# out8x8_2.net
KiCad netlist of a schematic drawn in EAGLE
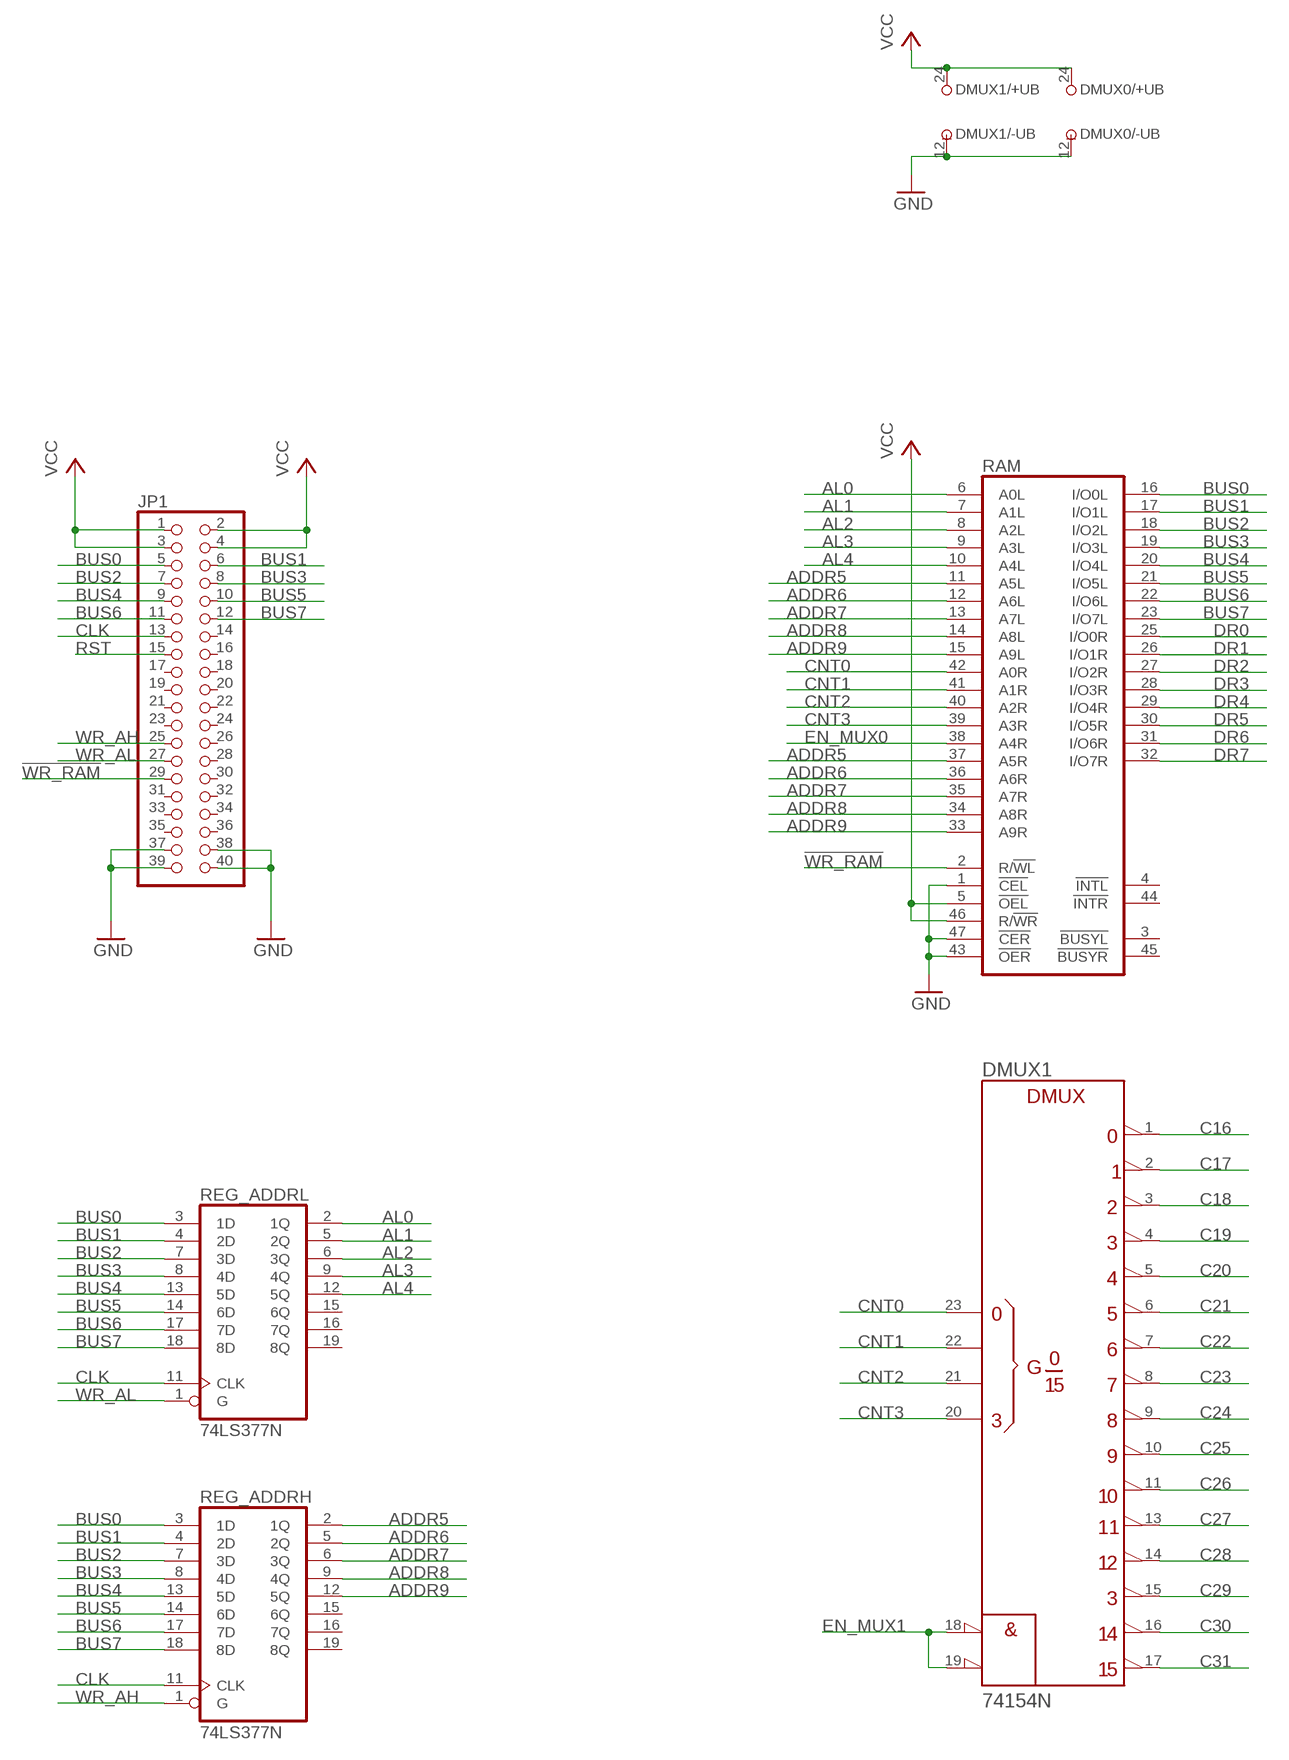
[diagram p0: schematic, sheet 1, part 1 of 2]
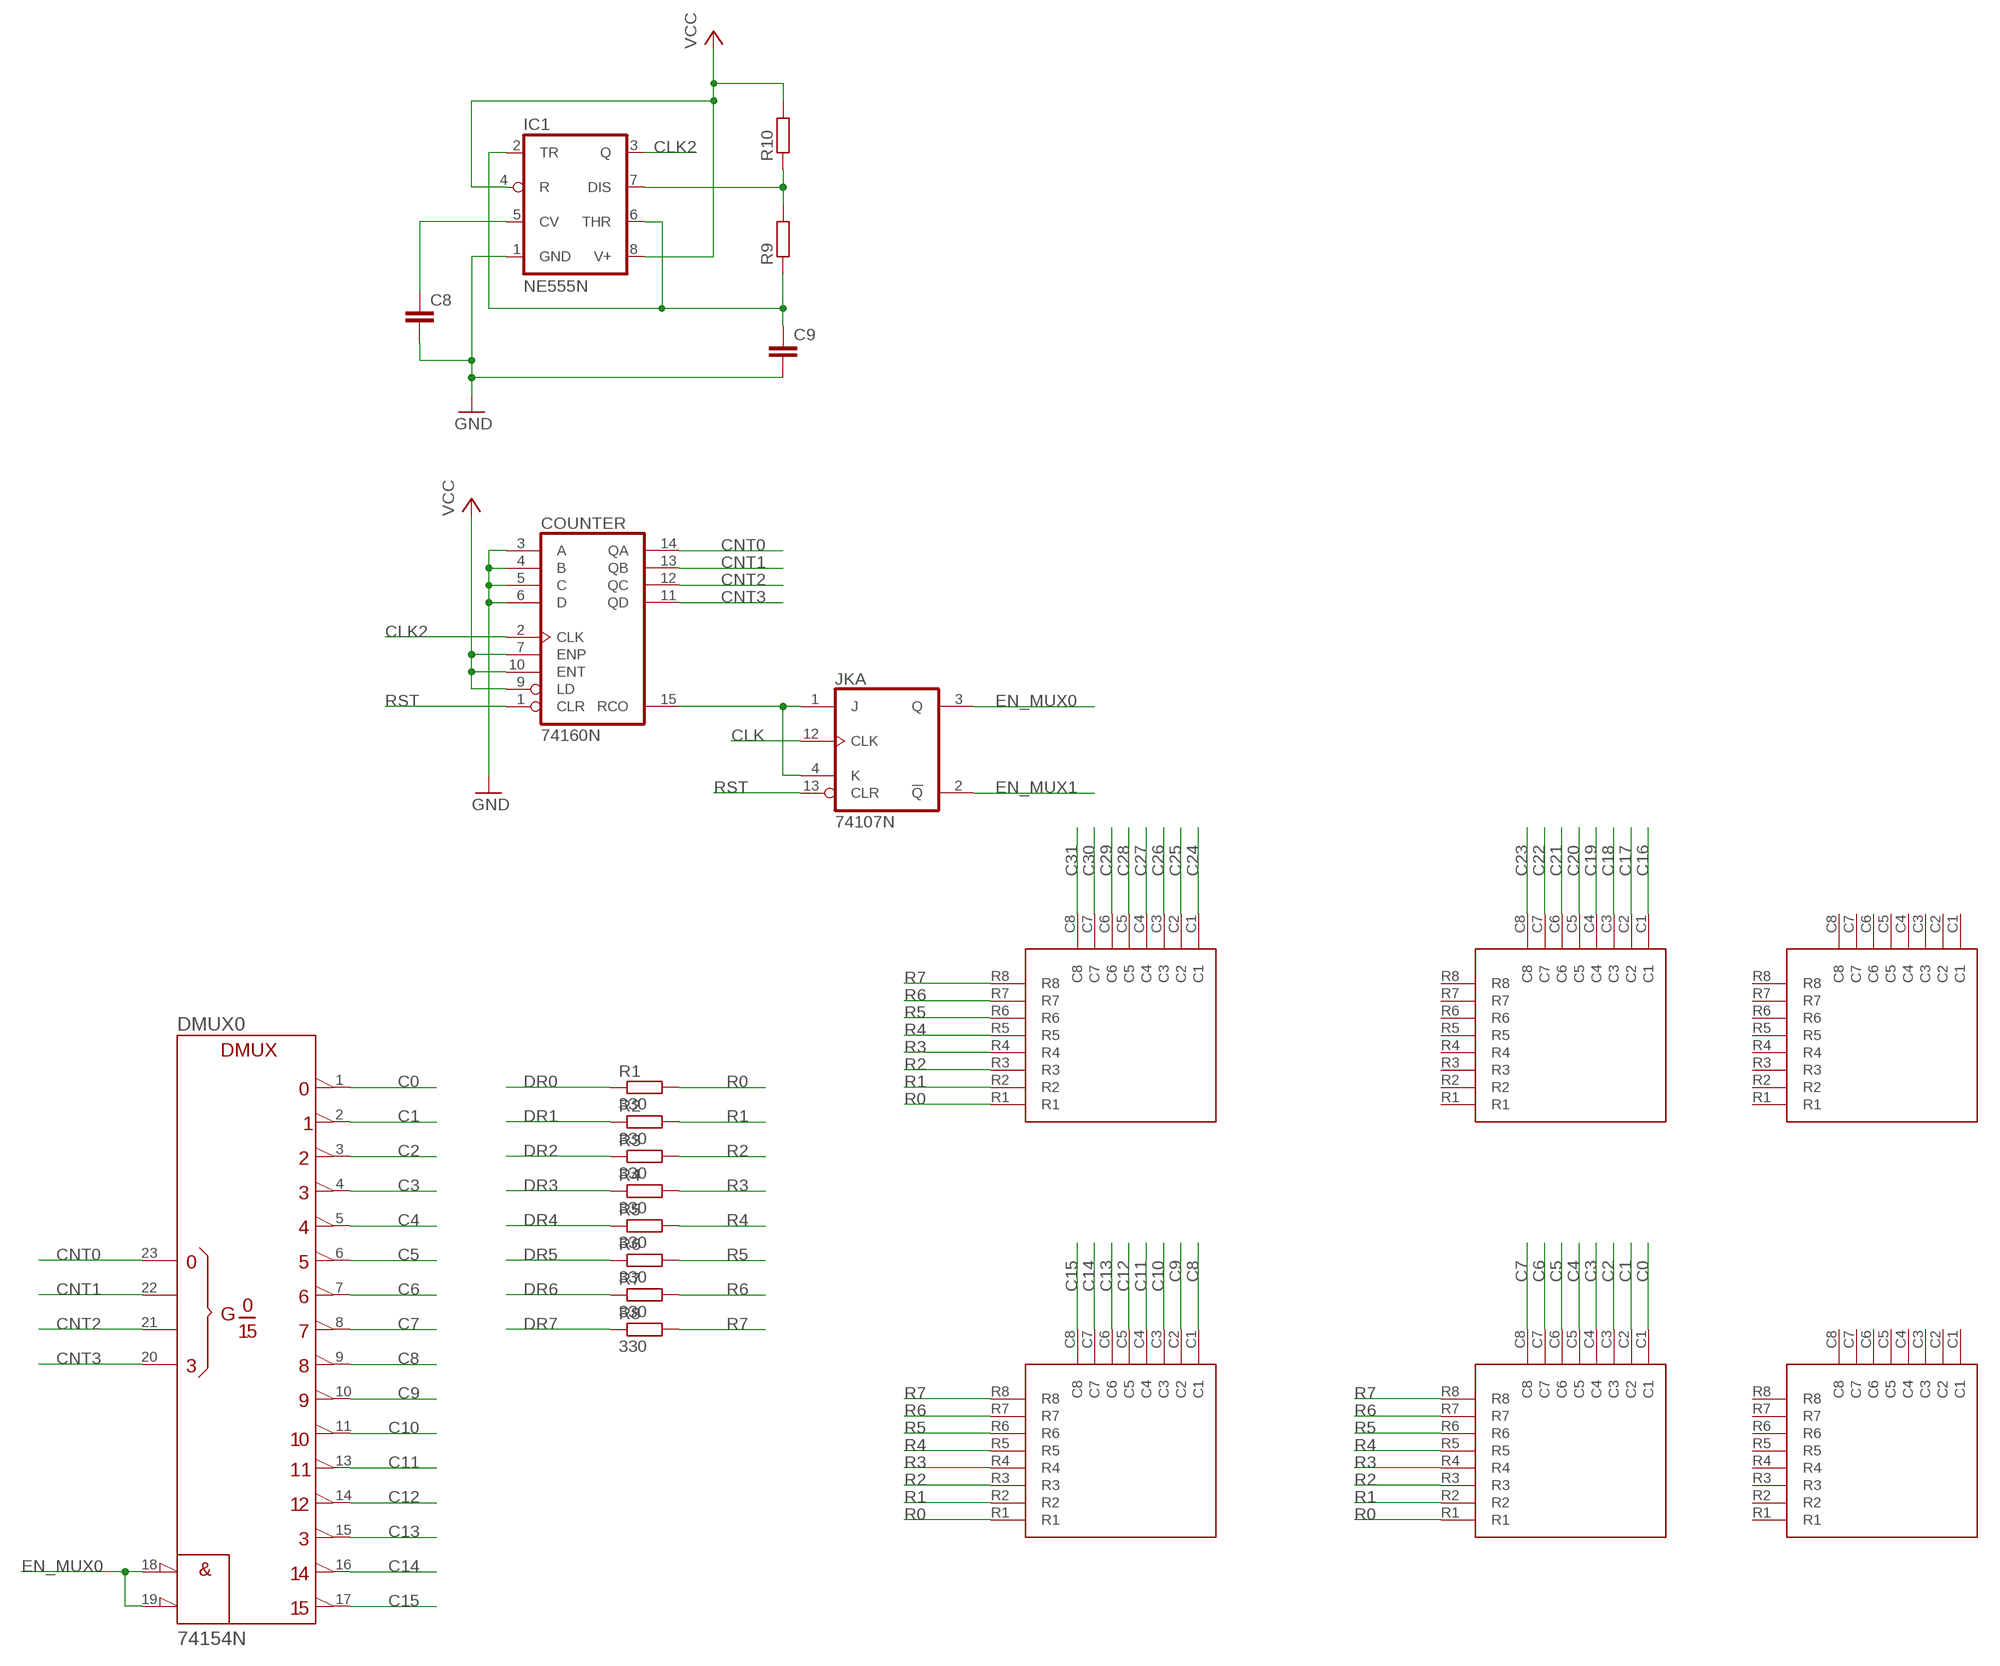
[diagram p1: schematic, sheet 1, part 2 of 2]

(export (version "E")
  (design (tool "Eeschema 10.0.6"))
  (components
    (comp (ref "C8")
      (value "C-EUC1206K")
      (footprint "eagle-import:C1206K")
      (libsource (lib "eagle-import") (part "C-EUC1206K"))
    )
    (comp (ref "C9")
      (value "C-EUC1206K")
      (footprint "eagle-import:C1206K")
      (libsource (lib "eagle-import") (part "C-EUC1206K"))
    )
    (comp (ref "COUNTER")
      (value "74160N")
      (footprint "eagle-import:DIL16")
      (libsource (lib "eagle-import") (part "74160N"))
    )
    (comp (ref "DMUX0")
      (value "74154N")
      (footprint "eagle-import:DIL24-3")
      (libsource (lib "eagle-import") (part "74154N"))
    )
    (comp (ref "DMUX1")
      (value "74154N")
      (footprint "eagle-import:DIL24-3")
      (libsource (lib "eagle-import") (part "74154N"))
    )
    (comp (ref "IC1")
      (value "NE555N")
      (footprint "eagle-import:DIL08")
      (libsource (lib "eagle-import") (part "555NNE"))
    )
    (comp (ref "JK")
      (value "74107N")
      (footprint "eagle-import:DIL14")
      (libsource (lib "eagle-import") (part "74107N"))
    )
    (comp (ref "JP1")
      (value "PINHD-2X20/90")
      (footprint "eagle-import:2X20_90")
      (libsource (lib "eagle-import") (part "PINHD-2X20/90"))
    )
    (comp (ref "R1")
      (value "330")
      (footprint "eagle-import:R0805")
      (libsource (lib "eagle-import") (part "R-EU_R0805"))
    )
    (comp (ref "R2")
      (value "330")
      (footprint "eagle-import:R0805")
      (libsource (lib "eagle-import") (part "R-EU_R0805"))
    )
    (comp (ref "R3")
      (value "330")
      (footprint "eagle-import:R0805")
      (libsource (lib "eagle-import") (part "R-EU_R0805"))
    )
    (comp (ref "R4")
      (value "330")
      (footprint "eagle-import:R0805")
      (libsource (lib "eagle-import") (part "R-EU_R0805"))
    )
    (comp (ref "R5")
      (value "330")
      (footprint "eagle-import:R0805")
      (libsource (lib "eagle-import") (part "R-EU_R0805"))
    )
    (comp (ref "R6")
      (value "330")
      (footprint "eagle-import:R0805")
      (libsource (lib "eagle-import") (part "R-EU_R0805"))
    )
    (comp (ref "R7")
      (value "330")
      (footprint "eagle-import:R0805")
      (libsource (lib "eagle-import") (part "R-EU_R0805"))
    )
    (comp (ref "R8")
      (value "330")
      (footprint "eagle-import:R0805")
      (libsource (lib "eagle-import") (part "R-EU_R0805"))
    )
    (comp (ref "R9")
      (value "R-EU_M1206")
      (footprint "eagle-import:M1206")
      (libsource (lib "eagle-import") (part "R-EU_M1206"))
    )
    (comp (ref "R10")
      (value "R-EU_M1206")
      (footprint "eagle-import:M1206")
      (libsource (lib "eagle-import") (part "R-EU_M1206"))
    )
    (comp (ref "RAM")
      (value "7130P")
      (footprint "eagle-import:DIL48")
      (libsource (lib "eagle-import") (part "7130P"))
    )
    (comp (ref "REG_ADDRH")
      (value "74LS377N")
      (footprint "eagle-import:DIL20")
      (libsource (lib "eagle-import") (part "74377NLS"))
    )
    (comp (ref "REG_ADDRL")
      (value "74LS377N")
      (footprint "eagle-import:DIL20")
      (libsource (lib "eagle-import") (part "74377NLS"))
    )
    (comp (ref "U$1")
      (value "LED8X8")
      (footprint "eagle-import:LED8X8")
      (libsource (lib "eagle-import") (part "LED8X8"))
    )
    (comp (ref "U$2")
      (value "LED8X8")
      (footprint "eagle-import:LED8X8")
      (libsource (lib "eagle-import") (part "LED8X8"))
    )
    (comp (ref "U$3")
      (value "LED8X8")
      (footprint "eagle-import:LED8X8")
      (libsource (lib "eagle-import") (part "LED8X8"))
    )
    (comp (ref "U$4")
      (value "LED8X8")
      (footprint "eagle-import:LED8X8")
      (libsource (lib "eagle-import") (part "LED8X8"))
    )
    (comp (ref "U$5")
      (value "LED8X8")
      (footprint "eagle-import:LED8X8")
      (libsource (lib "eagle-import") (part "LED8X8"))
    )
    (comp (ref "U$6")
      (value "LED8X8")
      (footprint "eagle-import:LED8X8")
      (libsource (lib "eagle-import") (part "LED8X8"))
    )
  )
  (nets
    (net (code "1") (name "/ADDR5") (class "Default")
      (node (ref "RAM") (pin "11") (pinfunction "A5L_11") (pintype "input"))
      (node (ref "RAM") (pin "37") (pinfunction "A5R_37") (pintype "input"))
      (node (ref "REG_ADDRH") (pin "2") (pinfunction "1Q_2") (pintype "output"))
    )
    (net (code "2") (name "/ADDR6") (class "Default")
      (node (ref "RAM") (pin "12") (pinfunction "A6L_12") (pintype "input"))
      (node (ref "RAM") (pin "36") (pinfunction "A6R_36") (pintype "input"))
      (node (ref "REG_ADDRH") (pin "5") (pinfunction "2Q_5") (pintype "output"))
    )
    (net (code "3") (name "/ADDR7") (class "Default")
      (node (ref "RAM") (pin "13") (pinfunction "A7L_13") (pintype "input"))
      (node (ref "RAM") (pin "35") (pinfunction "A7R_35") (pintype "input"))
      (node (ref "REG_ADDRH") (pin "6") (pinfunction "3Q_6") (pintype "output"))
    )
    (net (code "4") (name "/ADDR8") (class "Default")
      (node (ref "RAM") (pin "14") (pinfunction "A8L_14") (pintype "input"))
      (node (ref "RAM") (pin "34") (pinfunction "A8R_34") (pintype "input"))
      (node (ref "REG_ADDRH") (pin "9") (pinfunction "4Q_9") (pintype "output"))
    )
    (net (code "5") (name "/ADDR9") (class "Default")
      (node (ref "RAM") (pin "15") (pinfunction "A9L_15") (pintype "input"))
      (node (ref "RAM") (pin "33") (pinfunction "A9R_33") (pintype "input"))
      (node (ref "REG_ADDRH") (pin "12") (pinfunction "5Q_12") (pintype "output"))
    )
    (net (code "6") (name "/AL0") (class "Default")
      (node (ref "RAM") (pin "6") (pinfunction "A0L_6") (pintype "input"))
      (node (ref "REG_ADDRL") (pin "2") (pinfunction "1Q_2") (pintype "output"))
    )
    (net (code "7") (name "/AL1") (class "Default")
      (node (ref "RAM") (pin "7") (pinfunction "A1L_7") (pintype "input"))
      (node (ref "REG_ADDRL") (pin "5") (pinfunction "2Q_5") (pintype "output"))
    )
    (net (code "8") (name "/AL2") (class "Default")
      (node (ref "RAM") (pin "8") (pinfunction "A2L_8") (pintype "input"))
      (node (ref "REG_ADDRL") (pin "6") (pinfunction "3Q_6") (pintype "output"))
    )
    (net (code "9") (name "/AL3") (class "Default")
      (node (ref "RAM") (pin "9") (pinfunction "A3L_9") (pintype "input"))
      (node (ref "REG_ADDRL") (pin "9") (pinfunction "4Q_9") (pintype "output"))
    )
    (net (code "10") (name "/AL4") (class "Default")
      (node (ref "RAM") (pin "10") (pinfunction "A4L_10") (pintype "input"))
      (node (ref "REG_ADDRL") (pin "12") (pinfunction "5Q_12") (pintype "output"))
    )
    (net (code "11") (name "/BUS0") (class "Default")
      (node (ref "JP1") (pin "5") (pinfunction "5_5") (pintype "passive"))
      (node (ref "RAM") (pin "16") (pinfunction "I/O0L_16") (pintype "bidirectional"))
      (node (ref "REG_ADDRH") (pin "3") (pinfunction "1D_3") (pintype "input"))
      (node (ref "REG_ADDRL") (pin "3") (pinfunction "1D_3") (pintype "input"))
    )
    (net (code "12") (name "/BUS1") (class "Default")
      (node (ref "JP1") (pin "6") (pinfunction "6_6") (pintype "passive"))
      (node (ref "RAM") (pin "17") (pinfunction "I/O1L_17") (pintype "bidirectional"))
      (node (ref "REG_ADDRH") (pin "4") (pinfunction "2D_4") (pintype "input"))
      (node (ref "REG_ADDRL") (pin "4") (pinfunction "2D_4") (pintype "input"))
    )
    (net (code "13") (name "/BUS2") (class "Default")
      (node (ref "JP1") (pin "7") (pinfunction "7_7") (pintype "passive"))
      (node (ref "RAM") (pin "18") (pinfunction "I/O2L_18") (pintype "bidirectional"))
      (node (ref "REG_ADDRH") (pin "7") (pinfunction "3D_7") (pintype "input"))
      (node (ref "REG_ADDRL") (pin "7") (pinfunction "3D_7") (pintype "input"))
    )
    (net (code "14") (name "/BUS3") (class "Default")
      (node (ref "JP1") (pin "8") (pinfunction "8_8") (pintype "passive"))
      (node (ref "RAM") (pin "19") (pinfunction "I/O3L_19") (pintype "bidirectional"))
      (node (ref "REG_ADDRH") (pin "8") (pinfunction "4D_8") (pintype "input"))
      (node (ref "REG_ADDRL") (pin "8") (pinfunction "4D_8") (pintype "input"))
    )
    (net (code "15") (name "/BUS4") (class "Default")
      (node (ref "JP1") (pin "9") (pinfunction "9_9") (pintype "passive"))
      (node (ref "RAM") (pin "20") (pinfunction "I/O4L_20") (pintype "bidirectional"))
      (node (ref "REG_ADDRH") (pin "13") (pinfunction "5D_13") (pintype "input"))
      (node (ref "REG_ADDRL") (pin "13") (pinfunction "5D_13") (pintype "input"))
    )
    (net (code "16") (name "/BUS5") (class "Default")
      (node (ref "JP1") (pin "10") (pinfunction "10_10") (pintype "passive"))
      (node (ref "RAM") (pin "21") (pinfunction "I/O5L_21") (pintype "bidirectional"))
      (node (ref "REG_ADDRH") (pin "14") (pinfunction "6D_14") (pintype "input"))
      (node (ref "REG_ADDRL") (pin "14") (pinfunction "6D_14") (pintype "input"))
    )
    (net (code "17") (name "/BUS6") (class "Default")
      (node (ref "JP1") (pin "11") (pinfunction "11_11") (pintype "passive"))
      (node (ref "RAM") (pin "22") (pinfunction "I/O6L_22") (pintype "bidirectional"))
      (node (ref "REG_ADDRH") (pin "17") (pinfunction "7D_17") (pintype "input"))
      (node (ref "REG_ADDRL") (pin "17") (pinfunction "7D_17") (pintype "input"))
    )
    (net (code "18") (name "/BUS7") (class "Default")
      (node (ref "JP1") (pin "12") (pinfunction "12_12") (pintype "passive"))
      (node (ref "RAM") (pin "23") (pinfunction "I/O7L_23") (pintype "bidirectional"))
      (node (ref "REG_ADDRH") (pin "18") (pinfunction "8D_18") (pintype "input"))
      (node (ref "REG_ADDRL") (pin "18") (pinfunction "8D_18") (pintype "input"))
    )
    (net (code "19") (name "/C0") (class "Default")
      (node (ref "DMUX0") (pin "1") (pinfunction "0_1") (pintype "output"))
      (node (ref "U$4") (pin "C1") (pinfunction "C1_C1") (pintype "bidirectional"))
    )
    (net (code "20") (name "/C1") (class "Default")
      (node (ref "DMUX0") (pin "2") (pinfunction "1_2") (pintype "output"))
      (node (ref "U$4") (pin "C2") (pinfunction "C2_C2") (pintype "bidirectional"))
    )
    (net (code "21") (name "/C2") (class "Default")
      (node (ref "DMUX0") (pin "3") (pinfunction "2_3") (pintype "output"))
      (node (ref "U$4") (pin "C3") (pinfunction "C3_C3") (pintype "bidirectional"))
    )
    (net (code "22") (name "/C3") (class "Default")
      (node (ref "DMUX0") (pin "4") (pinfunction "3_4") (pintype "output"))
      (node (ref "U$4") (pin "C4") (pinfunction "C4_C4") (pintype "bidirectional"))
    )
    (net (code "23") (name "/C4") (class "Default")
      (node (ref "DMUX0") (pin "5") (pinfunction "4_5") (pintype "output"))
      (node (ref "U$4") (pin "C5") (pinfunction "C5_C5") (pintype "bidirectional"))
    )
    (net (code "24") (name "/C5") (class "Default")
      (node (ref "DMUX0") (pin "6") (pinfunction "5_6") (pintype "output"))
      (node (ref "U$4") (pin "C6") (pinfunction "C6_C6") (pintype "bidirectional"))
    )
    (net (code "25") (name "/C6") (class "Default")
      (node (ref "DMUX0") (pin "7") (pinfunction "6_7") (pintype "output"))
      (node (ref "U$4") (pin "C7") (pinfunction "C7_C7") (pintype "bidirectional"))
    )
    (net (code "26") (name "/C7") (class "Default")
      (node (ref "DMUX0") (pin "8") (pinfunction "7_8") (pintype "output"))
      (node (ref "U$4") (pin "C8") (pinfunction "C8_C8") (pintype "bidirectional"))
    )
    (net (code "27") (name "/C8") (class "Default")
      (node (ref "DMUX0") (pin "9") (pinfunction "8_9") (pintype "output"))
      (node (ref "U$3") (pin "C1") (pinfunction "C1_C1") (pintype "bidirectional"))
    )
    (net (code "28") (name "/C9") (class "Default")
      (node (ref "DMUX0") (pin "10") (pinfunction "9_10") (pintype "output"))
      (node (ref "U$3") (pin "C2") (pinfunction "C2_C2") (pintype "bidirectional"))
    )
    (net (code "29") (name "/C10") (class "Default")
      (node (ref "DMUX0") (pin "11") (pinfunction "10_11") (pintype "output"))
      (node (ref "U$3") (pin "C3") (pinfunction "C3_C3") (pintype "bidirectional"))
    )
    (net (code "30") (name "/C11") (class "Default")
      (node (ref "DMUX0") (pin "13") (pinfunction "11_13") (pintype "output"))
      (node (ref "U$3") (pin "C4") (pinfunction "C4_C4") (pintype "bidirectional"))
    )
    (net (code "31") (name "/C12") (class "Default")
      (node (ref "DMUX0") (pin "14") (pinfunction "12_14") (pintype "output"))
      (node (ref "U$3") (pin "C5") (pinfunction "C5_C5") (pintype "bidirectional"))
    )
    (net (code "32") (name "/C13") (class "Default")
      (node (ref "DMUX0") (pin "15") (pinfunction "13_15") (pintype "output"))
      (node (ref "U$3") (pin "C6") (pinfunction "C6_C6") (pintype "bidirectional"))
    )
    (net (code "33") (name "/C14") (class "Default")
      (node (ref "DMUX0") (pin "16") (pinfunction "14_16") (pintype "output"))
      (node (ref "U$3") (pin "C7") (pinfunction "C7_C7") (pintype "bidirectional"))
    )
    (net (code "34") (name "/C15") (class "Default")
      (node (ref "DMUX0") (pin "17") (pinfunction "15_17") (pintype "output"))
      (node (ref "U$3") (pin "C8") (pinfunction "C8_C8") (pintype "bidirectional"))
    )
    (net (code "35") (name "/C16") (class "Default")
      (node (ref "DMUX1") (pin "1") (pinfunction "0_1") (pintype "output"))
      (node (ref "U$1") (pin "C1") (pinfunction "C1_C1") (pintype "bidirectional"))
    )
    (net (code "36") (name "/C17") (class "Default")
      (node (ref "DMUX1") (pin "2") (pinfunction "1_2") (pintype "output"))
      (node (ref "U$1") (pin "C2") (pinfunction "C2_C2") (pintype "bidirectional"))
    )
    (net (code "37") (name "/C18") (class "Default")
      (node (ref "DMUX1") (pin "3") (pinfunction "2_3") (pintype "output"))
      (node (ref "U$1") (pin "C3") (pinfunction "C3_C3") (pintype "bidirectional"))
    )
    (net (code "38") (name "/C19") (class "Default")
      (node (ref "DMUX1") (pin "4") (pinfunction "3_4") (pintype "output"))
      (node (ref "U$1") (pin "C4") (pinfunction "C4_C4") (pintype "bidirectional"))
    )
    (net (code "39") (name "/C20") (class "Default")
      (node (ref "DMUX1") (pin "5") (pinfunction "4_5") (pintype "output"))
      (node (ref "U$1") (pin "C5") (pinfunction "C5_C5") (pintype "bidirectional"))
    )
    (net (code "40") (name "/C21") (class "Default")
      (node (ref "DMUX1") (pin "6") (pinfunction "5_6") (pintype "output"))
      (node (ref "U$1") (pin "C6") (pinfunction "C6_C6") (pintype "bidirectional"))
    )
    (net (code "41") (name "/C22") (class "Default")
      (node (ref "DMUX1") (pin "7") (pinfunction "6_7") (pintype "output"))
      (node (ref "U$1") (pin "C7") (pinfunction "C7_C7") (pintype "bidirectional"))
    )
    (net (code "42") (name "/C23") (class "Default")
      (node (ref "DMUX1") (pin "8") (pinfunction "7_8") (pintype "output"))
      (node (ref "U$1") (pin "C8") (pinfunction "C8_C8") (pintype "bidirectional"))
    )
    (net (code "43") (name "/C24") (class "Default")
      (node (ref "DMUX1") (pin "9") (pinfunction "8_9") (pintype "output"))
      (node (ref "U$2") (pin "C1") (pinfunction "C1_C1") (pintype "bidirectional"))
    )
    (net (code "44") (name "/C25") (class "Default")
      (node (ref "DMUX1") (pin "10") (pinfunction "9_10") (pintype "output"))
      (node (ref "U$2") (pin "C2") (pinfunction "C2_C2") (pintype "bidirectional"))
    )
    (net (code "45") (name "/C26") (class "Default")
      (node (ref "DMUX1") (pin "11") (pinfunction "10_11") (pintype "output"))
      (node (ref "U$2") (pin "C3") (pinfunction "C3_C3") (pintype "bidirectional"))
    )
    (net (code "46") (name "/C27") (class "Default")
      (node (ref "DMUX1") (pin "13") (pinfunction "11_13") (pintype "output"))
      (node (ref "U$2") (pin "C4") (pinfunction "C4_C4") (pintype "bidirectional"))
    )
    (net (code "47") (name "/C28") (class "Default")
      (node (ref "DMUX1") (pin "14") (pinfunction "12_14") (pintype "output"))
      (node (ref "U$2") (pin "C5") (pinfunction "C5_C5") (pintype "bidirectional"))
    )
    (net (code "48") (name "/C29") (class "Default")
      (node (ref "DMUX1") (pin "15") (pinfunction "13_15") (pintype "output"))
      (node (ref "U$2") (pin "C6") (pinfunction "C6_C6") (pintype "bidirectional"))
    )
    (net (code "49") (name "/C30") (class "Default")
      (node (ref "DMUX1") (pin "16") (pinfunction "14_16") (pintype "output"))
      (node (ref "U$2") (pin "C7") (pinfunction "C7_C7") (pintype "bidirectional"))
    )
    (net (code "50") (name "/C31") (class "Default")
      (node (ref "DMUX1") (pin "17") (pinfunction "15_17") (pintype "output"))
      (node (ref "U$2") (pin "C8") (pinfunction "C8_C8") (pintype "bidirectional"))
    )
    (net (code "51") (name "/CLK") (class "Default")
      (node (ref "JK") (pin "12") (pinfunction "CLK_12") (pintype "input"))
      (node (ref "JP1") (pin "13") (pinfunction "13_13") (pintype "passive"))
      (node (ref "REG_ADDRH") (pin "11") (pinfunction "CLK_11") (pintype "input"))
      (node (ref "REG_ADDRL") (pin "11") (pinfunction "CLK_11") (pintype "input"))
    )
    (net (code "52") (name "/CLK2") (class "Default")
      (node (ref "COUNTER") (pin "2") (pinfunction "CLK_2") (pintype "input"))
      (node (ref "IC1") (pin "3") (pinfunction "Q_3") (pintype "output"))
    )
    (net (code "53") (name "/CNT0") (class "Default")
      (node (ref "COUNTER") (pin "14") (pinfunction "QA_14") (pintype "output"))
      (node (ref "DMUX0") (pin "23") (pinfunction "A_23") (pintype "input"))
      (node (ref "DMUX1") (pin "23") (pinfunction "A_23") (pintype "input"))
      (node (ref "RAM") (pin "42") (pinfunction "A0R_42") (pintype "input"))
    )
    (net (code "54") (name "/CNT1") (class "Default")
      (node (ref "COUNTER") (pin "13") (pinfunction "QB_13") (pintype "output"))
      (node (ref "DMUX0") (pin "22") (pinfunction "B_22") (pintype "input"))
      (node (ref "DMUX1") (pin "22") (pinfunction "B_22") (pintype "input"))
      (node (ref "RAM") (pin "41") (pinfunction "A1R_41") (pintype "input"))
    )
    (net (code "55") (name "/CNT2") (class "Default")
      (node (ref "COUNTER") (pin "12") (pinfunction "QC_12") (pintype "output"))
      (node (ref "DMUX0") (pin "21") (pinfunction "C_21") (pintype "input"))
      (node (ref "DMUX1") (pin "21") (pinfunction "C_21") (pintype "input"))
      (node (ref "RAM") (pin "40") (pinfunction "A2R_40") (pintype "input"))
    )
    (net (code "56") (name "/CNT3") (class "Default")
      (node (ref "COUNTER") (pin "11") (pinfunction "QD_11") (pintype "output"))
      (node (ref "DMUX0") (pin "20") (pinfunction "D_20") (pintype "input"))
      (node (ref "DMUX1") (pin "20") (pinfunction "D_20") (pintype "input"))
      (node (ref "RAM") (pin "39") (pinfunction "A3R_39") (pintype "input"))
    )
    (net (code "57") (name "/DR0") (class "Default")
      (node (ref "R1") (pin "1") (pinfunction "1_1") (pintype "passive"))
      (node (ref "RAM") (pin "25") (pinfunction "I/O0R_25") (pintype "bidirectional"))
    )
    (net (code "58") (name "/DR1") (class "Default")
      (node (ref "R2") (pin "1") (pinfunction "1_1") (pintype "passive"))
      (node (ref "RAM") (pin "26") (pinfunction "I/O1R_26") (pintype "bidirectional"))
    )
    (net (code "59") (name "/DR2") (class "Default")
      (node (ref "R3") (pin "1") (pinfunction "1_1") (pintype "passive"))
      (node (ref "RAM") (pin "27") (pinfunction "I/O2R_27") (pintype "bidirectional"))
    )
    (net (code "60") (name "/DR3") (class "Default")
      (node (ref "R4") (pin "1") (pinfunction "1_1") (pintype "passive"))
      (node (ref "RAM") (pin "28") (pinfunction "I/O3R_28") (pintype "bidirectional"))
    )
    (net (code "61") (name "/DR4") (class "Default")
      (node (ref "R5") (pin "1") (pinfunction "1_1") (pintype "passive"))
      (node (ref "RAM") (pin "29") (pinfunction "I/O4R_29") (pintype "bidirectional"))
    )
    (net (code "62") (name "/DR5") (class "Default")
      (node (ref "R6") (pin "1") (pinfunction "1_1") (pintype "passive"))
      (node (ref "RAM") (pin "30") (pinfunction "I/O5R_30") (pintype "bidirectional"))
    )
    (net (code "63") (name "/DR6") (class "Default")
      (node (ref "R7") (pin "1") (pinfunction "1_1") (pintype "passive"))
      (node (ref "RAM") (pin "31") (pinfunction "I/O6R_31") (pintype "bidirectional"))
    )
    (net (code "64") (name "/DR7") (class "Default")
      (node (ref "R8") (pin "1") (pinfunction "1_1") (pintype "passive"))
      (node (ref "RAM") (pin "32") (pinfunction "I/O7R_32") (pintype "bidirectional"))
    )
    (net (code "65") (name "/EN_MUX0") (class "Default")
      (node (ref "DMUX0") (pin "18") (pinfunction "~{G1}_18") (pintype "input"))
      (node (ref "DMUX0") (pin "19") (pinfunction "~{G2}_19") (pintype "input"))
      (node (ref "JK") (pin "3") (pinfunction "Q_3") (pintype "output"))
      (node (ref "RAM") (pin "38") (pinfunction "A4R_38") (pintype "input"))
    )
    (net (code "66") (name "/EN_MUX1") (class "Default")
      (node (ref "DMUX1") (pin "18") (pinfunction "~{G1}_18") (pintype "input"))
      (node (ref "DMUX1") (pin "19") (pinfunction "~{G2}_19") (pintype "input"))
      (node (ref "JK") (pin "2") (pinfunction "~{Q}_2") (pintype "output"))
    )
    (net (code "67") (name "/R0") (class "Default")
      (node (ref "R1") (pin "2") (pinfunction "2_2") (pintype "passive"))
      (node (ref "U$2") (pin "R1") (pinfunction "R1_R1") (pintype "bidirectional"))
      (node (ref "U$3") (pin "R1") (pinfunction "R1_R1") (pintype "bidirectional"))
      (node (ref "U$4") (pin "R1") (pinfunction "R1_R1") (pintype "bidirectional"))
    )
    (net (code "68") (name "/R1") (class "Default")
      (node (ref "R2") (pin "2") (pinfunction "2_2") (pintype "passive"))
      (node (ref "U$2") (pin "R2") (pinfunction "R2_R2") (pintype "bidirectional"))
      (node (ref "U$3") (pin "R2") (pinfunction "R2_R2") (pintype "bidirectional"))
      (node (ref "U$4") (pin "R2") (pinfunction "R2_R2") (pintype "bidirectional"))
    )
    (net (code "69") (name "/R2") (class "Default")
      (node (ref "R3") (pin "2") (pinfunction "2_2") (pintype "passive"))
      (node (ref "U$2") (pin "R3") (pinfunction "R3_R3") (pintype "bidirectional"))
      (node (ref "U$3") (pin "R3") (pinfunction "R3_R3") (pintype "bidirectional"))
      (node (ref "U$4") (pin "R3") (pinfunction "R3_R3") (pintype "bidirectional"))
    )
    (net (code "70") (name "/R3") (class "Default")
      (node (ref "R4") (pin "2") (pinfunction "2_2") (pintype "passive"))
      (node (ref "U$2") (pin "R4") (pinfunction "R4_R4") (pintype "bidirectional"))
      (node (ref "U$3") (pin "R4") (pinfunction "R4_R4") (pintype "bidirectional"))
      (node (ref "U$4") (pin "R4") (pinfunction "R4_R4") (pintype "bidirectional"))
    )
    (net (code "71") (name "/R4") (class "Default")
      (node (ref "R5") (pin "2") (pinfunction "2_2") (pintype "passive"))
      (node (ref "U$2") (pin "R5") (pinfunction "R5_R5") (pintype "bidirectional"))
      (node (ref "U$3") (pin "R5") (pinfunction "R5_R5") (pintype "bidirectional"))
      (node (ref "U$4") (pin "R5") (pinfunction "R5_R5") (pintype "bidirectional"))
    )
    (net (code "72") (name "/R5") (class "Default")
      (node (ref "R6") (pin "2") (pinfunction "2_2") (pintype "passive"))
      (node (ref "U$2") (pin "R6") (pinfunction "R6_R6") (pintype "bidirectional"))
      (node (ref "U$3") (pin "R6") (pinfunction "R6_R6") (pintype "bidirectional"))
      (node (ref "U$4") (pin "R6") (pinfunction "R6_R6") (pintype "bidirectional"))
    )
    (net (code "73") (name "/R6") (class "Default")
      (node (ref "R7") (pin "2") (pinfunction "2_2") (pintype "passive"))
      (node (ref "U$2") (pin "R7") (pinfunction "R7_R7") (pintype "bidirectional"))
      (node (ref "U$3") (pin "R7") (pinfunction "R7_R7") (pintype "bidirectional"))
      (node (ref "U$4") (pin "R7") (pinfunction "R7_R7") (pintype "bidirectional"))
    )
    (net (code "74") (name "/R7") (class "Default")
      (node (ref "R8") (pin "2") (pinfunction "2_2") (pintype "passive"))
      (node (ref "U$2") (pin "R8") (pinfunction "R8_R8") (pintype "bidirectional"))
      (node (ref "U$3") (pin "R8") (pinfunction "R8_R8") (pintype "bidirectional"))
      (node (ref "U$4") (pin "R8") (pinfunction "R8_R8") (pintype "bidirectional"))
    )
    (net (code "75") (name "/RST") (class "Default")
      (node (ref "COUNTER") (pin "1") (pinfunction "CLR_1") (pintype "input"))
      (node (ref "JK") (pin "13") (pinfunction "CLR_13") (pintype "input"))
      (node (ref "JP1") (pin "15") (pinfunction "15_15") (pintype "passive"))
    )
    (net (code "76") (name "/WR_AH") (class "Default")
      (node (ref "JP1") (pin "25") (pinfunction "25_25") (pintype "passive"))
      (node (ref "REG_ADDRH") (pin "1") (pinfunction "G_1") (pintype "input"))
    )
    (net (code "77") (name "/WR_AL") (class "Default")
      (node (ref "JP1") (pin "27") (pinfunction "27_27") (pintype "passive"))
      (node (ref "REG_ADDRL") (pin "1") (pinfunction "G_1") (pintype "input"))
    )
    (net (code "78") (name "/~{WR_RAM}") (class "Default")
      (node (ref "JP1") (pin "29") (pinfunction "29_29") (pintype "passive"))
      (node (ref "RAM") (pin "2") (pinfunction "R/~{WL}_2") (pintype "input"))
    )
    (net (code "79") (name "GND") (class "Default")
      (node (ref "C8") (pin "2") (pinfunction "2_2") (pintype "passive"))
      (node (ref "C9") (pin "2") (pinfunction "2_2") (pintype "passive"))
      (node (ref "COUNTER") (pin "3") (pinfunction "A_3") (pintype "input"))
      (node (ref "COUNTER") (pin "4") (pinfunction "B_4") (pintype "input"))
      (node (ref "COUNTER") (pin "5") (pinfunction "C_5") (pintype "input"))
      (node (ref "COUNTER") (pin "6") (pinfunction "D_6") (pintype "input"))
      (node (ref "DMUX0") (pin "12") (pinfunction "-UB_12") (pintype "power_in"))
      (node (ref "DMUX1") (pin "12") (pinfunction "-UB_12") (pintype "power_in"))
      (node (ref "IC1") (pin "1") (pinfunction "GND_1") (pintype "power_in"))
      (node (ref "JP1") (pin "37") (pinfunction "37_37") (pintype "passive"))
      (node (ref "JP1") (pin "38") (pinfunction "38_38") (pintype "passive"))
      (node (ref "JP1") (pin "39") (pinfunction "39_39") (pintype "passive"))
      (node (ref "JP1") (pin "40") (pinfunction "40_40") (pintype "passive"))
      (node (ref "RAM") (pin "1") (pinfunction "~{CEL}_1") (pintype "input"))
      (node (ref "RAM") (pin "43") (pinfunction "~{OER}_43") (pintype "input"))
      (node (ref "RAM") (pin "47") (pinfunction "~{CER}_47") (pintype "input"))
    )
    (net (code "80") (name "Net-(COUNTERA-RCO)") (class "Default")
      (node (ref "COUNTER") (pin "15") (pinfunction "RCO_15") (pintype "output"))
      (node (ref "JK") (pin "1") (pinfunction "J_1") (pintype "input"))
      (node (ref "JK") (pin "4") (pinfunction "K_4") (pintype "input"))
    )
    (net (code "81") (name "Net-(IC1-CV)") (class "Default")
      (node (ref "C8") (pin "1") (pinfunction "1_1") (pintype "passive"))
      (node (ref "IC1") (pin "5") (pinfunction "CV_5") (pintype "input"))
    )
    (net (code "82") (name "Net-(IC1-DIS)") (class "Default")
      (node (ref "IC1") (pin "7") (pinfunction "DIS_7") (pintype "input"))
      (node (ref "R10") (pin "1") (pinfunction "1_1") (pintype "passive"))
      (node (ref "R9") (pin "2") (pinfunction "2_2") (pintype "passive"))
    )
    (net (code "83") (name "Net-(IC1-THR)") (class "Default")
      (node (ref "C9") (pin "1") (pinfunction "1_1") (pintype "passive"))
      (node (ref "IC1") (pin "2") (pinfunction "TR_2") (pintype "input"))
      (node (ref "IC1") (pin "6") (pinfunction "THR_6") (pintype "input"))
      (node (ref "R9") (pin "1") (pinfunction "1_1") (pintype "passive"))
    )
    (net (code "84") (name "VCC") (class "Default")
      (node (ref "COUNTER") (pin "10") (pinfunction "ENT_10") (pintype "input"))
      (node (ref "COUNTER") (pin "7") (pinfunction "ENP_7") (pintype "input"))
      (node (ref "COUNTER") (pin "9") (pinfunction "LD_9") (pintype "input"))
      (node (ref "DMUX0") (pin "24") (pinfunction "+UB_24") (pintype "power_in"))
      (node (ref "DMUX1") (pin "24") (pinfunction "+UB_24") (pintype "power_in"))
      (node (ref "IC1") (pin "4") (pinfunction "R_4") (pintype "input"))
      (node (ref "IC1") (pin "8") (pinfunction "V+_8") (pintype "power_in"))
      (node (ref "JP1") (pin "1") (pinfunction "1_1") (pintype "passive"))
      (node (ref "JP1") (pin "2") (pinfunction "2_2") (pintype "passive"))
      (node (ref "JP1") (pin "3") (pinfunction "3_3") (pintype "passive"))
      (node (ref "JP1") (pin "4") (pinfunction "4_4") (pintype "passive"))
      (node (ref "R10") (pin "2") (pinfunction "2_2") (pintype "passive"))
      (node (ref "RAM") (pin "46") (pinfunction "R/~{WR}_46") (pintype "input"))
      (node (ref "RAM") (pin "5") (pinfunction "~{OEL}_5") (pintype "input"))
    )
    (net (code "85") (name "unconnected-(JP1-Pad14)") (class "Default")
      (node (ref "JP1") (pin "14") (pinfunction "14_14") (pintype "passive"))
    )
    (net (code "86") (name "unconnected-(JP1-Pad16)") (class "Default")
      (node (ref "JP1") (pin "16") (pinfunction "16_16") (pintype "passive"))
    )
    (net (code "87") (name "unconnected-(JP1-Pad17)") (class "Default")
      (node (ref "JP1") (pin "17") (pinfunction "17_17") (pintype "passive"))
    )
    (net (code "88") (name "unconnected-(JP1-Pad18)") (class "Default")
      (node (ref "JP1") (pin "18") (pinfunction "18_18") (pintype "passive"))
    )
    (net (code "89") (name "unconnected-(JP1-Pad19)") (class "Default")
      (node (ref "JP1") (pin "19") (pinfunction "19_19") (pintype "passive"))
    )
    (net (code "90") (name "unconnected-(JP1-Pad20)") (class "Default")
      (node (ref "JP1") (pin "20") (pinfunction "20_20") (pintype "passive"))
    )
    (net (code "91") (name "unconnected-(JP1-Pad21)") (class "Default")
      (node (ref "JP1") (pin "21") (pinfunction "21_21") (pintype "passive"))
    )
    (net (code "92") (name "unconnected-(JP1-Pad22)") (class "Default")
      (node (ref "JP1") (pin "22") (pinfunction "22_22") (pintype "passive"))
    )
    (net (code "93") (name "unconnected-(JP1-Pad23)") (class "Default")
      (node (ref "JP1") (pin "23") (pinfunction "23_23") (pintype "passive"))
    )
    (net (code "94") (name "unconnected-(JP1-Pad24)") (class "Default")
      (node (ref "JP1") (pin "24") (pinfunction "24_24") (pintype "passive"))
    )
    (net (code "95") (name "unconnected-(JP1-Pad26)") (class "Default")
      (node (ref "JP1") (pin "26") (pinfunction "26_26") (pintype "passive"))
    )
    (net (code "96") (name "unconnected-(JP1-Pad28)") (class "Default")
      (node (ref "JP1") (pin "28") (pinfunction "28_28") (pintype "passive"))
    )
    (net (code "97") (name "unconnected-(JP1-Pad30)") (class "Default")
      (node (ref "JP1") (pin "30") (pinfunction "30_30") (pintype "passive"))
    )
    (net (code "98") (name "unconnected-(JP1-Pad31)") (class "Default")
      (node (ref "JP1") (pin "31") (pinfunction "31_31") (pintype "passive"))
    )
    (net (code "99") (name "unconnected-(JP1-Pad32)") (class "Default")
      (node (ref "JP1") (pin "32") (pinfunction "32_32") (pintype "passive"))
    )
    (net (code "100") (name "unconnected-(JP1-Pad33)") (class "Default")
      (node (ref "JP1") (pin "33") (pinfunction "33_33") (pintype "passive"))
    )
    (net (code "101") (name "unconnected-(JP1-Pad34)") (class "Default")
      (node (ref "JP1") (pin "34") (pinfunction "34_34") (pintype "passive"))
    )
    (net (code "102") (name "unconnected-(JP1-Pad35)") (class "Default")
      (node (ref "JP1") (pin "35") (pinfunction "35_35") (pintype "passive"))
    )
    (net (code "103") (name "unconnected-(JP1-Pad36)") (class "Default")
      (node (ref "JP1") (pin "36") (pinfunction "36_36") (pintype "passive"))
    )
    (net (code "104") (name "unconnected-(RAMA-~{BUSYL}-Pad3)") (class "Default")
      (node (ref "RAM") (pin "3") (pinfunction "~{BUSYL}_3") (pintype "bidirectional"))
    )
    (net (code "105") (name "unconnected-(RAMA-~{BUSYR}-Pad45)") (class "Default")
      (node (ref "RAM") (pin "45") (pinfunction "~{BUSYR}_45") (pintype "bidirectional"))
    )
    (net (code "106") (name "unconnected-(RAMA-~{INTL}-Pad4)") (class "Default")
      (node (ref "RAM") (pin "4") (pinfunction "~{INTL}_4") (pintype "output"))
    )
    (net (code "107") (name "unconnected-(RAMA-~{INTR}-Pad44)") (class "Default")
      (node (ref "RAM") (pin "44") (pinfunction "~{INTR}_44") (pintype "output"))
    )
    (net (code "108") (name "unconnected-(REG_ADDRHA-6Q-Pad15)") (class "Default")
      (node (ref "REG_ADDRH") (pin "15") (pinfunction "6Q_15") (pintype "output"))
    )
    (net (code "109") (name "unconnected-(REG_ADDRHA-7Q-Pad16)") (class "Default")
      (node (ref "REG_ADDRH") (pin "16") (pinfunction "7Q_16") (pintype "output"))
    )
    (net (code "110") (name "unconnected-(REG_ADDRHA-8Q-Pad19)") (class "Default")
      (node (ref "REG_ADDRH") (pin "19") (pinfunction "8Q_19") (pintype "output"))
    )
    (net (code "111") (name "unconnected-(REG_ADDRLA-6Q-Pad15)") (class "Default")
      (node (ref "REG_ADDRL") (pin "15") (pinfunction "6Q_15") (pintype "output"))
    )
    (net (code "112") (name "unconnected-(REG_ADDRLA-7Q-Pad16)") (class "Default")
      (node (ref "REG_ADDRL") (pin "16") (pinfunction "7Q_16") (pintype "output"))
    )
    (net (code "113") (name "unconnected-(REG_ADDRLA-8Q-Pad19)") (class "Default")
      (node (ref "REG_ADDRL") (pin "19") (pinfunction "8Q_19") (pintype "output"))
    )
    (net (code "114") (name "unconnected-(U$1-PadR1)") (class "Default")
      (node (ref "U$1") (pin "R1") (pinfunction "R1_R1") (pintype "bidirectional"))
    )
    (net (code "115") (name "unconnected-(U$1-PadR2)") (class "Default")
      (node (ref "U$1") (pin "R2") (pinfunction "R2_R2") (pintype "bidirectional"))
    )
    (net (code "116") (name "unconnected-(U$1-PadR3)") (class "Default")
      (node (ref "U$1") (pin "R3") (pinfunction "R3_R3") (pintype "bidirectional"))
    )
    (net (code "117") (name "unconnected-(U$1-PadR4)") (class "Default")
      (node (ref "U$1") (pin "R4") (pinfunction "R4_R4") (pintype "bidirectional"))
    )
    (net (code "118") (name "unconnected-(U$1-PadR5)") (class "Default")
      (node (ref "U$1") (pin "R5") (pinfunction "R5_R5") (pintype "bidirectional"))
    )
    (net (code "119") (name "unconnected-(U$1-PadR6)") (class "Default")
      (node (ref "U$1") (pin "R6") (pinfunction "R6_R6") (pintype "bidirectional"))
    )
    (net (code "120") (name "unconnected-(U$1-PadR7)") (class "Default")
      (node (ref "U$1") (pin "R7") (pinfunction "R7_R7") (pintype "bidirectional"))
    )
    (net (code "121") (name "unconnected-(U$1-PadR8)") (class "Default")
      (node (ref "U$1") (pin "R8") (pinfunction "R8_R8") (pintype "bidirectional"))
    )
    (net (code "122") (name "unconnected-(U$5-PadC1)") (class "Default")
      (node (ref "U$5") (pin "C1") (pinfunction "C1_C1") (pintype "bidirectional"))
    )
    (net (code "123") (name "unconnected-(U$5-PadC2)") (class "Default")
      (node (ref "U$5") (pin "C2") (pinfunction "C2_C2") (pintype "bidirectional"))
    )
    (net (code "124") (name "unconnected-(U$5-PadC3)") (class "Default")
      (node (ref "U$5") (pin "C3") (pinfunction "C3_C3") (pintype "bidirectional"))
    )
    (net (code "125") (name "unconnected-(U$5-PadC4)") (class "Default")
      (node (ref "U$5") (pin "C4") (pinfunction "C4_C4") (pintype "bidirectional"))
    )
    (net (code "126") (name "unconnected-(U$5-PadC5)") (class "Default")
      (node (ref "U$5") (pin "C5") (pinfunction "C5_C5") (pintype "bidirectional"))
    )
    (net (code "127") (name "unconnected-(U$5-PadC6)") (class "Default")
      (node (ref "U$5") (pin "C6") (pinfunction "C6_C6") (pintype "bidirectional"))
    )
    (net (code "128") (name "unconnected-(U$5-PadC7)") (class "Default")
      (node (ref "U$5") (pin "C7") (pinfunction "C7_C7") (pintype "bidirectional"))
    )
    (net (code "129") (name "unconnected-(U$5-PadC8)") (class "Default")
      (node (ref "U$5") (pin "C8") (pinfunction "C8_C8") (pintype "bidirectional"))
    )
    (net (code "130") (name "unconnected-(U$5-PadR1)") (class "Default")
      (node (ref "U$5") (pin "R1") (pinfunction "R1_R1") (pintype "bidirectional"))
    )
    (net (code "131") (name "unconnected-(U$5-PadR2)") (class "Default")
      (node (ref "U$5") (pin "R2") (pinfunction "R2_R2") (pintype "bidirectional"))
    )
    (net (code "132") (name "unconnected-(U$5-PadR3)") (class "Default")
      (node (ref "U$5") (pin "R3") (pinfunction "R3_R3") (pintype "bidirectional"))
    )
    (net (code "133") (name "unconnected-(U$5-PadR4)") (class "Default")
      (node (ref "U$5") (pin "R4") (pinfunction "R4_R4") (pintype "bidirectional"))
    )
    (net (code "134") (name "unconnected-(U$5-PadR5)") (class "Default")
      (node (ref "U$5") (pin "R5") (pinfunction "R5_R5") (pintype "bidirectional"))
    )
    (net (code "135") (name "unconnected-(U$5-PadR6)") (class "Default")
      (node (ref "U$5") (pin "R6") (pinfunction "R6_R6") (pintype "bidirectional"))
    )
    (net (code "136") (name "unconnected-(U$5-PadR7)") (class "Default")
      (node (ref "U$5") (pin "R7") (pinfunction "R7_R7") (pintype "bidirectional"))
    )
    (net (code "137") (name "unconnected-(U$5-PadR8)") (class "Default")
      (node (ref "U$5") (pin "R8") (pinfunction "R8_R8") (pintype "bidirectional"))
    )
    (net (code "138") (name "unconnected-(U$6-PadC1)") (class "Default")
      (node (ref "U$6") (pin "C1") (pinfunction "C1_C1") (pintype "bidirectional"))
    )
    (net (code "139") (name "unconnected-(U$6-PadC2)") (class "Default")
      (node (ref "U$6") (pin "C2") (pinfunction "C2_C2") (pintype "bidirectional"))
    )
    (net (code "140") (name "unconnected-(U$6-PadC3)") (class "Default")
      (node (ref "U$6") (pin "C3") (pinfunction "C3_C3") (pintype "bidirectional"))
    )
    (net (code "141") (name "unconnected-(U$6-PadC4)") (class "Default")
      (node (ref "U$6") (pin "C4") (pinfunction "C4_C4") (pintype "bidirectional"))
    )
    (net (code "142") (name "unconnected-(U$6-PadC5)") (class "Default")
      (node (ref "U$6") (pin "C5") (pinfunction "C5_C5") (pintype "bidirectional"))
    )
    (net (code "143") (name "unconnected-(U$6-PadC6)") (class "Default")
      (node (ref "U$6") (pin "C6") (pinfunction "C6_C6") (pintype "bidirectional"))
    )
    (net (code "144") (name "unconnected-(U$6-PadC7)") (class "Default")
      (node (ref "U$6") (pin "C7") (pinfunction "C7_C7") (pintype "bidirectional"))
    )
    (net (code "145") (name "unconnected-(U$6-PadC8)") (class "Default")
      (node (ref "U$6") (pin "C8") (pinfunction "C8_C8") (pintype "bidirectional"))
    )
    (net (code "146") (name "unconnected-(U$6-PadR1)") (class "Default")
      (node (ref "U$6") (pin "R1") (pinfunction "R1_R1") (pintype "bidirectional"))
    )
    (net (code "147") (name "unconnected-(U$6-PadR2)") (class "Default")
      (node (ref "U$6") (pin "R2") (pinfunction "R2_R2") (pintype "bidirectional"))
    )
    (net (code "148") (name "unconnected-(U$6-PadR3)") (class "Default")
      (node (ref "U$6") (pin "R3") (pinfunction "R3_R3") (pintype "bidirectional"))
    )
    (net (code "149") (name "unconnected-(U$6-PadR4)") (class "Default")
      (node (ref "U$6") (pin "R4") (pinfunction "R4_R4") (pintype "bidirectional"))
    )
    (net (code "150") (name "unconnected-(U$6-PadR5)") (class "Default")
      (node (ref "U$6") (pin "R5") (pinfunction "R5_R5") (pintype "bidirectional"))
    )
    (net (code "151") (name "unconnected-(U$6-PadR6)") (class "Default")
      (node (ref "U$6") (pin "R6") (pinfunction "R6_R6") (pintype "bidirectional"))
    )
    (net (code "152") (name "unconnected-(U$6-PadR7)") (class "Default")
      (node (ref "U$6") (pin "R7") (pinfunction "R7_R7") (pintype "bidirectional"))
    )
    (net (code "153") (name "unconnected-(U$6-PadR8)") (class "Default")
      (node (ref "U$6") (pin "R8") (pinfunction "R8_R8") (pintype "bidirectional"))
    )
  )
)
